# Sheet1.net
KiCad netlist of a schematic drawn in Altium Designer
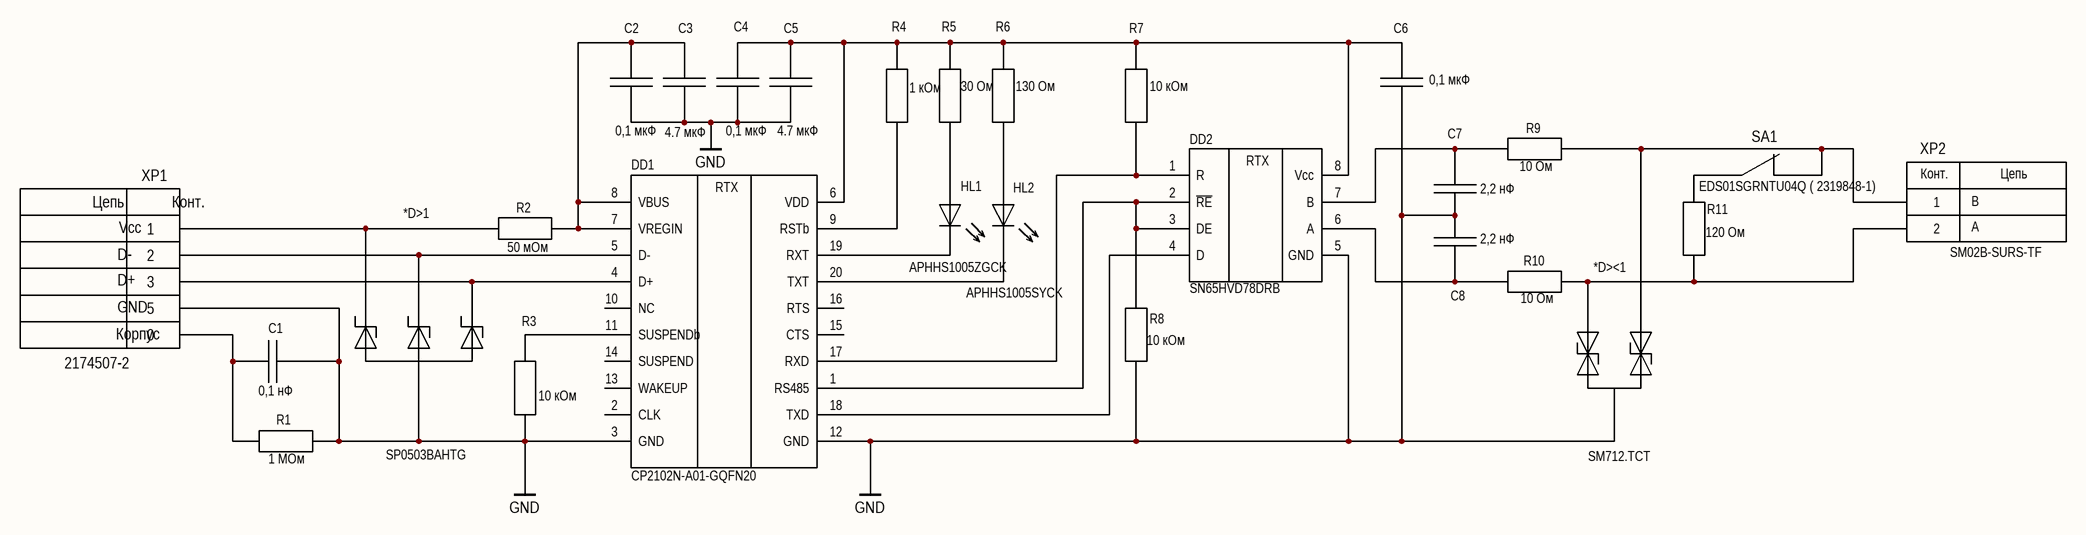
[diagram p0: Sheet1.SchDoc]

(export (version "E")
  (design (tool "Eeschema 10.0.6"))
  (components
    (comp (ref "*D>1")
      (value "Диод лавинный сборкаSP0503BAHTGsot-143Littelfuse")
      (footprint "PcbLib1:SOT190P237X122-4N")
      (description "Unidirectional TVS Array")
      (fields (field (name "PARTNUMBER") "SP0503BAHTG") (field (name "MANUFACTURER") "Littelfuse"))
      (libsource (lib "altium-import") (part "root_1_SP0503BAHTG_"))
    )
    (comp (ref "*D><1")
      (value "Диод лавинный сборкаSM712.TCTsot-23-3Semtech")
      (footprint "PcbLib1:SOT95P237X112-3L")
      (description "TVS Diode for RS-485")
      (fields (field (name "PARTNUMBER") "SM712.TCT") (field (name "MANUFACTURER") "Semtech"))
      (libsource (lib "altium-import") (part "root_1_SM712.TCT_"))
    )
    (comp (ref "C1")
      (value "capasistor")
      (footprint "PcbLib1:CAP0805")
      (fields
        (field (name "MANUFACTURER") "Kemet")
        (field (name "PARTNUMBER") "C0805C101MDRACTU")
        (field (name "CAPACITY") "0,1 нФ")
        (field (name "TOLERANCE") "20%")
      )
      (libsource (lib "altium-import") (part "root_2_CAP_"))
    )
    (comp (ref "C2")
      (value "capasistor")
      (footprint "PcbLib1:CAP0402")
      (fields
        (field (name "MANUFACTURER") "Murata")
        (field (name "PARTNUMBER") "GRM033R61A104ME15D")
        (field (name "CAPACITY") "0,1 мкФ")
        (field (name "TOLERANCE") "20%")
      )
      (libsource (lib "altium-import") (part "root_1_CAP_"))
    )
    (comp (ref "C3")
      (value "capasistor")
      (footprint "PcbLib1:CAP0402")
      (fields
        (field (name "MANUFACTURER") "Murata")
        (field (name "PARTNUMBER") "GRM155R61A475MEAAD")
        (field (name "CAPACITY") "4.7 мкФ")
        (field (name "TOLERANCE") "20%")
      )
      (libsource (lib "altium-import") (part "root_1_CAP_"))
    )
    (comp (ref "C4")
      (value "capasistor")
      (footprint "PcbLib1:CAP0402")
      (fields
        (field (name "MANUFACTURER") "Murata")
        (field (name "PARTNUMBER") "GRM033R61A104ME15D")
        (field (name "CAPACITY") "0,1 мкФ")
        (field (name "TOLERANCE") "20%")
      )
      (libsource (lib "altium-import") (part "root_1_CAP_"))
    )
    (comp (ref "C5")
      (value "capasistor")
      (footprint "PcbLib1:CAP0402")
      (fields
        (field (name "MANUFACTURER") "Murata")
        (field (name "PARTNUMBER") "GRM155R61A475MEAAD")
        (field (name "CAPACITY") "4.7 мкФ")
        (field (name "TOLERANCE") "20%")
      )
      (libsource (lib "altium-import") (part "root_1_CAP_"))
    )
    (comp (ref "C6")
      (value "capasistor")
      (footprint "PcbLib1:CAP0402")
      (fields
        (field (name "MANUFACTURER") "Murata")
        (field (name "PARTNUMBER") "GRM033R61A104ME15D")
        (field (name "CAPACITY") "0,1 мкФ")
        (field (name "TOLERANCE") "20%")
      )
      (libsource (lib "altium-import") (part "root_1_CAP_"))
    )
    (comp (ref "C7")
      (value "capasistor")
      (footprint "PcbLib1:CAP0402")
      (fields
        (field (name "MANUFACTURER") "Murata")
        (field (name "PARTNUMBER") "GRM155R61A222KA01D")
        (field (name "CAPACITY") "2,2 нФ")
        (field (name "TOLERANCE") "10%")
      )
      (libsource (lib "altium-import") (part "root_1_CAP_"))
    )
    (comp (ref "C8")
      (value "capasistor")
      (footprint "PcbLib1:CAP0402")
      (fields
        (field (name "MANUFACTURER") "Murata")
        (field (name "PARTNUMBER") "GRM155R61A222KA01D")
        (field (name "CAPACITY") "2,2 нФ")
        (field (name "TOLERANCE") "10%")
      )
      (libsource (lib "altium-import") (part "root_1_CAP_"))
    )
    (comp (ref "DD1")
      (value "CP2102N-A01-GQFN20")
      (footprint "PcbLib1:QFN50P300X300X80_HS-17L")
      (description "USB-to-UART bridge")
      (fields (field (name "MANUFACTURER") "Silicon Laboratories"))
      (libsource (lib "Schlib1") (part "CP2102N-A01-GQFN20"))
    )
    (comp (ref "DD2")
      (value "SN65HVD78DRB")
      (footprint "PcbLib1:SON65P300X100_HS-9L")
      (description "RS-485 With IEC ESD Protection")
      (fields (field (name "MANUFACTURER") "Texas Instruments"))
      (libsource (lib "altium-import") (part "root_0_SN65HVD78DRB_"))
    )
    (comp (ref "HL1")
      (value "APHHS1005ZGCK")
      (footprint "PcbLib1:LED0402")
      (description "LED GREEN SMD 1.0X0.5MM")
      (fields (field (name "MANUFACTURER") "Kingbright"))
      (libsource (lib "altium-import") (part "root_3_APHHS1005ZGCK_"))
    )
    (comp (ref "HL2")
      (value "APHHS1005SYCK")
      (footprint "PcbLib1:LED0402")
      (description "LED GREEN SMD 1.0X0.5MM")
      (fields (field (name "PARTNUMBER") "APHHS1005SYCK") (field (name "MANUFACTURER") "Kingbright"))
      (libsource (lib "altium-import") (part "root_3_APHHS1005ZGCK_"))
    )
    (comp (ref "R1")
      (value "resistor")
      (footprint "PcbLib1:RES0402")
      (fields
        (field (name "PARTNUMBER") "RC0402JR-071ML")
        (field (name "RESISRANCE") "1 МОм")
        (field (name "TOLERANCE") "5%")
        (field (name "MANUFACTURER") "Yageo")
      )
      (libsource (lib "altium-import") (part "root_2_RES_"))
    )
    (comp (ref "R2")
      (value "resistor")
      (footprint "PcbLib1:RES0402")
      (fields
        (field (name "PARTNUMBER") "RL0402FR-070R05L")
        (field (name "RESISRANCE") "50 мОм")
        (field (name "TOLERANCE") "1%")
        (field (name "MANUFACTURER") "Yageo")
      )
      (libsource (lib "altium-import") (part "root_2_RES_"))
    )
    (comp (ref "R3")
      (value "resistor")
      (footprint "PcbLib1:RES0402")
      (fields
        (field (name "PARTNUMBER") "RC0402JR-0710KL")
        (field (name "RESISRANCE") "10 кОм")
        (field (name "TOLERANCE") "5%")
        (field (name "MANUFACTURER") "Yageo")
      )
      (libsource (lib "altium-import") (part "root_1_RES_"))
    )
    (comp (ref "R4")
      (value "resistor")
      (footprint "PcbLib1:RES0402")
      (fields
        (field (name "PARTNUMBER") "RC0402JR-071KL")
        (field (name "RESISRANCE") "1 кОм")
        (field (name "TOLERANCE") "5%")
        (field (name "MANUFACTURER") "Yageo")
      )
      (libsource (lib "altium-import") (part "root_1_RES_"))
    )
    (comp (ref "R5")
      (value "resistor")
      (footprint "PcbLib1:RES0402")
      (fields
        (field (name "PARTNUMBER") "RC0402JR-0730RL")
        (field (name "RESISRANCE") "30 Ом")
        (field (name "TOLERANCE") "5%")
        (field (name "MANUFACTURER") "Yageo")
      )
      (libsource (lib "altium-import") (part "root_1_RES_"))
    )
    (comp (ref "R6")
      (value "resistor")
      (footprint "PcbLib1:RES0402")
      (fields
        (field (name "PARTNUMBER") "RC0402JR-07130RL")
        (field (name "RESISRANCE") "130 Ом")
        (field (name "TOLERANCE") "5%")
        (field (name "MANUFACTURER") "Yageo")
      )
      (libsource (lib "altium-import") (part "root_1_RES_"))
    )
    (comp (ref "R7")
      (value "resistor")
      (footprint "PcbLib1:RES0402")
      (fields
        (field (name "PARTNUMBER") "RC0402JR-0710KL")
        (field (name "RESISRANCE") "10 кОм")
        (field (name "TOLERANCE") "5%")
        (field (name "MANUFACTURER") "Yageo")
      )
      (libsource (lib "altium-import") (part "root_1_RES_"))
    )
    (comp (ref "R8")
      (value "resistor")
      (footprint "PcbLib1:RES0402")
      (fields
        (field (name "PARTNUMBER") "RC0402JR-0710KL")
        (field (name "RESISRANCE") "10 кОм")
        (field (name "TOLERANCE") "5%")
        (field (name "MANUFACTURER") "Yageo")
      )
      (libsource (lib "altium-import") (part "root_1_RES_"))
    )
    (comp (ref "R9")
      (value "resistor")
      (footprint "PcbLib1:RES0402")
      (fields
        (field (name "PARTNUMBER") "RC0402JR-0710RL")
        (field (name "RESISRANCE") "10 Ом")
        (field (name "TOLERANCE") "5%")
        (field (name "MANUFACTURER") "Yageo")
      )
      (libsource (lib "altium-import") (part "root_2_RES_"))
    )
    (comp (ref "R10")
      (value "resistor")
      (footprint "PcbLib1:RES0402")
      (fields
        (field (name "PARTNUMBER") "RC0402JR-0710RL")
        (field (name "RESISRANCE") "10 Ом")
        (field (name "TOLERANCE") "5%")
        (field (name "MANUFACTURER") "Yageo")
      )
      (libsource (lib "altium-import") (part "root_2_RES_"))
    )
    (comp (ref "R11")
      (value "resistor")
      (footprint "PcbLib1:RES0402")
      (fields
        (field (name "PARTNUMBER") "RC0402JR-07120RL")
        (field (name "RESISRANCE") "120 Ом")
        (field (name "TOLERANCE") "5%")
        (field (name "MANUFACTURER") "Yageo")
      )
      (libsource (lib "altium-import") (part "root_3_RES_"))
    )
    (comp (ref "SA1")
      (value "EDS01SGRNTU04Q ( 2319848-1)")
      (footprint "PcbLib1:SWITCH_TE")
      (description "Dip-switch")
      (fields (field (name "MANUFACTURER") "TE") (field (name "PARTNUMBER") "EDS01SGRNTU04Q ( 2319848-1)"))
      (libsource (lib "Schlib1") (part "EDS01SGRNTU04Q"))
    )
    (comp (ref "XP1")
      (value "ГнездоTE connectivity2174507-2")
      (footprint "PcbLib1:2174507-2")
      (description "MICRO USB, TYPE B")
      (fields (field (name "PARTNUMBER") "2174507-2") (field (name "MANUFACTURER") "TE connectivity"))
      (libsource (lib "Schlib1") (part "MICRO USB, TYPE B"))
    )
    (comp (ref "XP2")
      (value "connector")
      (footprint "PcbLib1:CONN_JST_SUH_02")
      (description "2 pin")
      (fields (field (name "MANUFACTURER") "JST") (field (name "PARTNUMBER") "SM02B-SURS-TF"))
      (libsource (lib "Schlib1") (part "CONN_02P"))
    )
  )
  (nets
    (net (code "1") (name "GND") (class "Default")
      (node (ref "*D>1") (pin "1") (pinfunction "Catod_1") (pintype "passive"))
      (node (ref "*D><1") (pin "3") (pinfunction "Catod_3") (pintype "passive"))
      (node (ref "C1") (pin "1") (pinfunction "1_1") (pintype "passive"))
      (node (ref "C2") (pin "1") (pinfunction "1_1") (pintype "passive"))
      (node (ref "C3") (pin "1") (pinfunction "1_1") (pintype "passive"))
      (node (ref "C4") (pin "1") (pinfunction "1_1") (pintype "passive"))
      (node (ref "C5") (pin "1") (pinfunction "1_1") (pintype "passive"))
      (node (ref "C6") (pin "1") (pinfunction "1_1") (pintype "passive"))
      (node (ref "C7") (pin "1") (pinfunction "1_1") (pintype "passive"))
      (node (ref "C8") (pin "2") (pinfunction "2_2") (pintype "passive"))
      (node (ref "DD1") (pin "12") (pinfunction "GND_12") (pintype "passive"))
      (node (ref "DD1") (pin "3") (pinfunction "GND_3") (pintype "passive"))
      (node (ref "DD2") (pin "5") (pinfunction "GND_5") (pintype "passive"))
      (node (ref "R1") (pin "1") (pinfunction "1_1") (pintype "passive"))
      (node (ref "R3") (pin "1") (pinfunction "1_1") (pintype "passive"))
      (node (ref "R8") (pin "1") (pinfunction "1_1") (pintype "passive"))
      (node (ref "XP1") (pin "5") (pinfunction "5_5") (pintype "passive"))
    )
    (net (code "2") (name "Net-(*D>1-Catod-Pad2)") (class "Default")
      (node (ref "*D>1") (pin "2") (pinfunction "Catod_2") (pintype "passive"))
      (node (ref "R2") (pin "2") (pinfunction "2_2") (pintype "passive"))
      (node (ref "XP1") (pin "1") (pinfunction "1_1") (pintype "passive"))
    )
    (net (code "3") (name "Net-(*D><1-Catod-Pad1)") (class "Default")
      (node (ref "*D><1") (pin "1") (pinfunction "Catod_1") (pintype "passive"))
      (node (ref "R10") (pin "1") (pinfunction "1_1") (pintype "passive"))
      (node (ref "R11") (pin "2") (pinfunction "2_2") (pintype "passive"))
      (node (ref "XP2") (pin "2") (pinfunction "2_2") (pintype "passive"))
    )
    (net (code "4") (name "Net-(*D><1-Catos)") (class "Default")
      (node (ref "*D><1") (pin "2") (pinfunction "Catos_2") (pintype "passive"))
      (node (ref "R9") (pin "1") (pinfunction "1_1") (pintype "passive"))
      (node (ref "SA1") (pin "2") (pinfunction "2_2") (pintype "passive"))
      (node (ref "XP2") (pin "1") (pinfunction "1_1") (pintype "passive"))
    )
    (net (code "5") (name "Net-(C1-Pad2)") (class "Default")
      (node (ref "C1") (pin "2") (pinfunction "2_2") (pintype "passive"))
      (node (ref "R1") (pin "2") (pinfunction "2_2") (pintype "passive"))
      (node (ref "XP1") (pin "0") (pinfunction "0_0") (pintype "passive"))
    )
    (net (code "6") (name "Net-(DD1-D+)") (class "Default")
      (node (ref "*D>1") (pin "4") (pinfunction "Catos_4") (pintype "passive"))
      (node (ref "DD1") (pin "4") (pinfunction "D+_4") (pintype "passive"))
      (node (ref "XP1") (pin "3") (pinfunction "3_3") (pintype "passive"))
    )
    (net (code "7") (name "Net-(DD1-D-)") (class "Default")
      (node (ref "*D>1") (pin "3") (pinfunction "Catos_3") (pintype "passive"))
      (node (ref "DD1") (pin "5") (pinfunction "D-_5") (pintype "passive"))
      (node (ref "XP1") (pin "2") (pinfunction "2_2") (pintype "passive"))
    )
    (net (code "8") (name "Net-(DD1-RS485)") (class "Default")
      (node (ref "DD1") (pin "1") (pinfunction "RS485_1") (pintype "passive"))
      (node (ref "DD2") (pin "2") (pinfunction "RE_2") (pintype "passive"))
      (node (ref "DD2") (pin "3") (pinfunction "DE_3") (pintype "passive"))
      (node (ref "R8") (pin "2") (pinfunction "2_2") (pintype "passive"))
    )
    (net (code "9") (name "Net-(DD1-RSTb)") (class "Default")
      (node (ref "DD1") (pin "9") (pinfunction "RSTb_9") (pintype "passive"))
      (node (ref "R4") (pin "1") (pinfunction "1_1") (pintype "passive"))
    )
    (net (code "10") (name "Net-(DD1-RXD)") (class "Default")
      (node (ref "DD1") (pin "17") (pinfunction "RXD_17") (pintype "passive"))
      (node (ref "DD2") (pin "1") (pinfunction "R_1") (pintype "passive"))
      (node (ref "R7") (pin "1") (pinfunction "1_1") (pintype "passive"))
    )
    (net (code "11") (name "Net-(DD1-RXT)") (class "Default")
      (node (ref "DD1") (pin "19") (pinfunction "RXT_19") (pintype "passive"))
      (node (ref "HL1") (pin "1") (pinfunction "K_1") (pintype "passive"))
    )
    (net (code "12") (name "Net-(DD1-SUSPENDb)") (class "Default")
      (node (ref "DD1") (pin "11") (pinfunction "SUSPENDb_11") (pintype "passive"))
      (node (ref "R3") (pin "2") (pinfunction "2_2") (pintype "passive"))
    )
    (net (code "13") (name "Net-(DD1-TXD)") (class "Default")
      (node (ref "DD1") (pin "18") (pinfunction "TXD_18") (pintype "passive"))
      (node (ref "DD2") (pin "4") (pinfunction "D_4") (pintype "passive"))
    )
    (net (code "14") (name "Net-(DD1-TXT)") (class "Default")
      (node (ref "DD1") (pin "20") (pinfunction "TXT_20") (pintype "passive"))
      (node (ref "HL2") (pin "1") (pinfunction "K_1") (pintype "passive"))
    )
    (net (code "15") (name "Net-(DD1-VBUS)") (class "Default")
      (node (ref "C2") (pin "2") (pinfunction "2_2") (pintype "passive"))
      (node (ref "C3") (pin "2") (pinfunction "2_2") (pintype "passive"))
      (node (ref "DD1") (pin "7") (pinfunction "VREGIN_7") (pintype "passive"))
      (node (ref "DD1") (pin "8") (pinfunction "VBUS_8") (pintype "passive"))
      (node (ref "R2") (pin "1") (pinfunction "1_1") (pintype "passive"))
    )
    (net (code "16") (name "Net-(DD1-VDD)") (class "Default")
      (node (ref "C4") (pin "2") (pinfunction "2_2") (pintype "passive"))
      (node (ref "C5") (pin "2") (pinfunction "2_2") (pintype "passive"))
      (node (ref "C6") (pin "2") (pinfunction "2_2") (pintype "passive"))
      (node (ref "DD1") (pin "6") (pinfunction "VDD_6") (pintype "passive"))
      (node (ref "DD2") (pin "8") (pinfunction "Vcc_8") (pintype "passive"))
      (node (ref "R4") (pin "2") (pinfunction "2_2") (pintype "passive"))
      (node (ref "R5") (pin "2") (pinfunction "2_2") (pintype "passive"))
      (node (ref "R6") (pin "2") (pinfunction "2_2") (pintype "passive"))
      (node (ref "R7") (pin "2") (pinfunction "2_2") (pintype "passive"))
    )
    (net (code "17") (name "Net-(DD2-A)") (class "Default")
      (node (ref "C8") (pin "1") (pinfunction "1_1") (pintype "passive"))
      (node (ref "DD2") (pin "6") (pinfunction "A_6") (pintype "passive"))
      (node (ref "R10") (pin "2") (pinfunction "2_2") (pintype "passive"))
    )
    (net (code "18") (name "Net-(DD2-B)") (class "Default")
      (node (ref "C7") (pin "2") (pinfunction "2_2") (pintype "passive"))
      (node (ref "DD2") (pin "7") (pinfunction "B_7") (pintype "passive"))
      (node (ref "R9") (pin "2") (pinfunction "2_2") (pintype "passive"))
    )
    (net (code "19") (name "Net-(HL1-A)") (class "Default")
      (node (ref "HL1") (pin "2") (pinfunction "A_2") (pintype "passive"))
      (node (ref "R5") (pin "1") (pinfunction "1_1") (pintype "passive"))
    )
    (net (code "20") (name "Net-(HL2-A)") (class "Default")
      (node (ref "HL2") (pin "2") (pinfunction "A_2") (pintype "passive"))
      (node (ref "R6") (pin "1") (pinfunction "1_1") (pintype "passive"))
    )
    (net (code "21") (name "Net-(R11-Pad1)") (class "Default")
      (node (ref "R11") (pin "1") (pinfunction "1_1") (pintype "passive"))
      (node (ref "SA1") (pin "1") (pinfunction "1_1") (pintype "passive"))
    )
    (net (code "22") (name "unconnected-(DD1-CLK-Pad2)") (class "Default")
      (node (ref "DD1") (pin "2") (pinfunction "CLK_2") (pintype "passive"))
    )
    (net (code "23") (name "unconnected-(DD1-CTS-Pad15)") (class "Default")
      (node (ref "DD1") (pin "15") (pinfunction "CTS_15") (pintype "passive"))
    )
    (net (code "24") (name "unconnected-(DD1-NC-Pad10)") (class "Default")
      (node (ref "DD1") (pin "10") (pinfunction "NC_10") (pintype "passive"))
    )
    (net (code "25") (name "unconnected-(DD1-RTS-Pad16)") (class "Default")
      (node (ref "DD1") (pin "16") (pinfunction "RTS_16") (pintype "passive"))
    )
    (net (code "26") (name "unconnected-(DD1-SUSPEND-Pad14)") (class "Default")
      (node (ref "DD1") (pin "14") (pinfunction "SUSPEND_14") (pintype "passive"))
    )
    (net (code "27") (name "unconnected-(DD1-WAKEUP-Pad13)") (class "Default")
      (node (ref "DD1") (pin "13") (pinfunction "WAKEUP_13") (pintype "passive"))
    )
  )
)
